# Power_Supply.net
KiCad netlist of a schematic drawn in Altium Designer
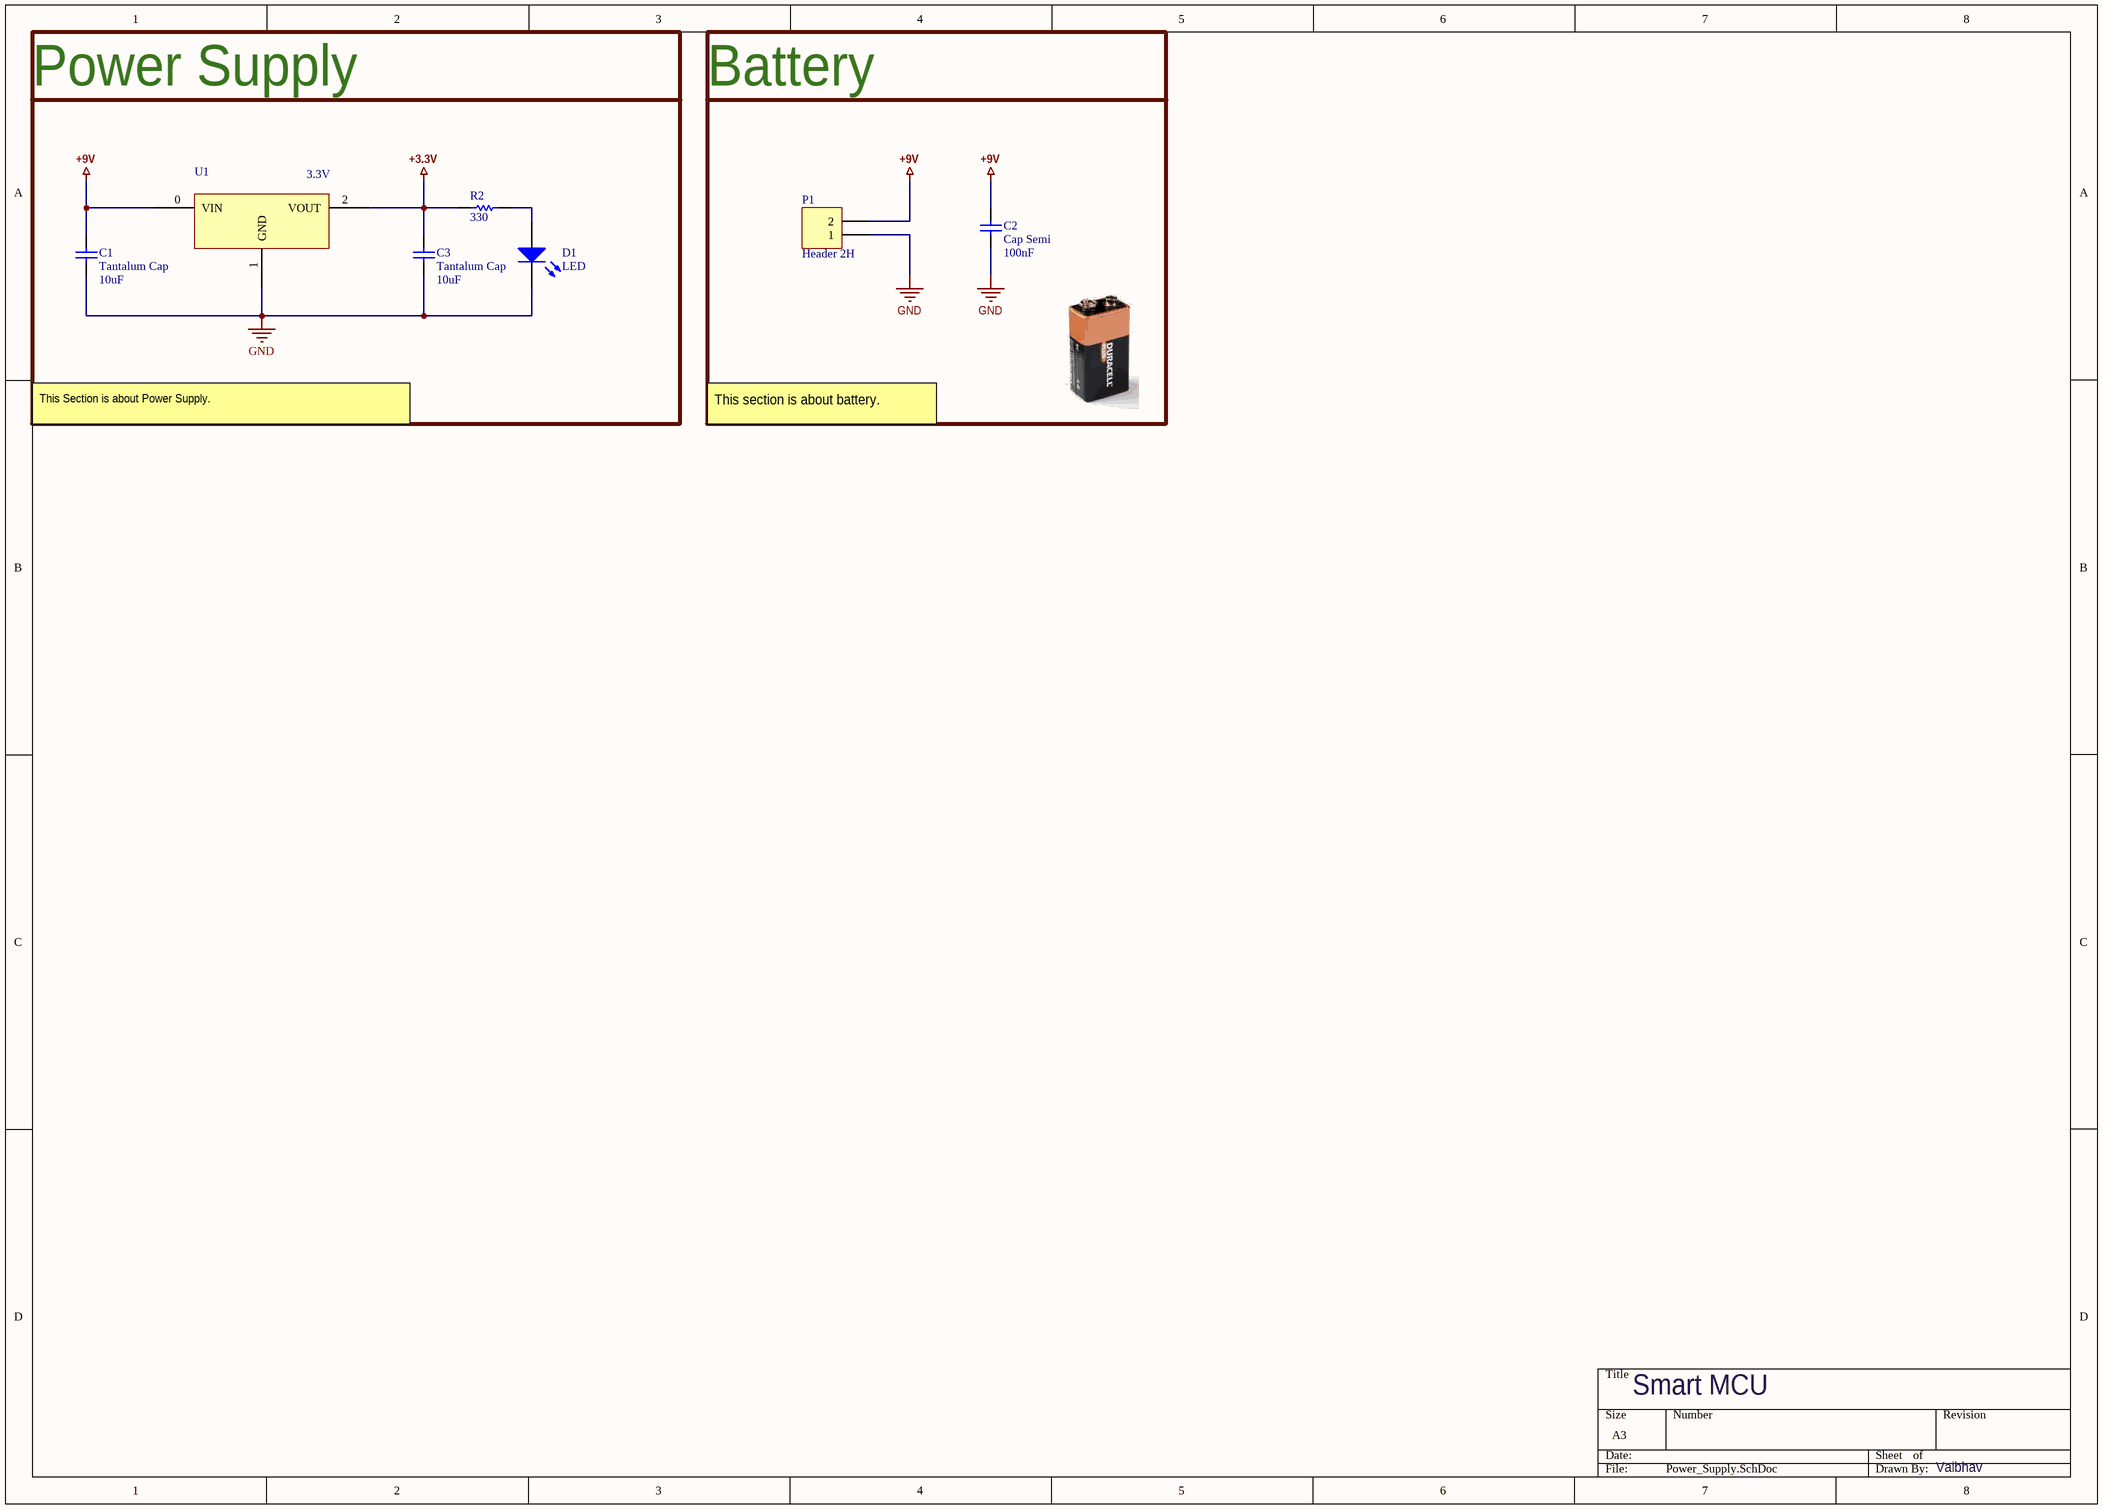
[diagram p0: Power_Supply.SchDoc]

(export (version "E")
  (design (tool "Eeschema 10.0.6"))
  (components
    (comp (ref "C1")
      (value "Tantalum Cap")
      (footprint "C1206")
      (description "Capacitor (Semiconductor SIM Model)")
      (fields (field (name "ALTIUM_VALUE") "10uF") (field (name "PUBLISHER") "Altium Limited"))
      (libsource (lib "Miscellaneous Devices") (part "Cap Semi"))
    )
    (comp (ref "C2")
      (value "Cap Semi")
      (footprint "C1206")
      (description "Capacitor (Semiconductor SIM Model)")
      (fields (field (name "ALTIUM_VALUE") "100nF") (field (name "PUBLISHER") "Altium Limited"))
      (libsource (lib "Miscellaneous Devices") (part "Cap Semi"))
    )
    (comp (ref "C3")
      (value "Tantalum Cap")
      (footprint "C1206")
      (description "Capacitor (Semiconductor SIM Model)")
      (fields (field (name "ALTIUM_VALUE") "10uF") (field (name "PUBLISHER") "Altium Limited"))
      (libsource (lib "Miscellaneous Devices") (part "Cap Semi"))
    )
    (comp (ref "D1")
      (value "LED")
      (footprint "MY_LED_0805")
      (description "Typical INFRARED GaAs LED")
      (fields (field (name "ASID PART NUMBER") "LED-AS"))
      (libsource (lib "Mylib+Rev+4") (part "LED"))
    )
    (comp (ref "P1")
      (value "Header 2H")
      (footprint "HDR1X2H")
      (description "Header, 2-Pin, Right Angle")
      (fields (field (name "PUBLISHER") "Altium Limited"))
      (libsource (lib "Miscellaneous Connectors") (part "Header 2H"))
    )
    (comp (ref "R2")
      (value "330")
      (footprint "MY_0805")
      (description "Standard resistor")
      (fields (field (name "ASID PART NUMBER") "Res-AS"))
      (libsource (lib "Mylib+Rev+4") (part "Res"))
    )
    (comp (ref "U1")
      (value "~")
      (footprint "4-Pin SOT")
      (fields (field (name "OUTPUT VOLTAG") "3.3V"))
      (libsource (lib "Smart MCU") (part "lm1117"))
    )
  )
  (nets
    (net (code "1") (name "+3.3V") (class "Default")
      (node (ref "C3") (pin "2") (pinfunction "2_2") (pintype "passive"))
      (node (ref "R2") (pin "1") (pinfunction "1_1") (pintype "passive"))
      (node (ref "U1") (pin "2") (pinfunction "VOUT_2") (pintype "passive"))
    )
    (net (code "2") (name "+9V") (class "Default")
      (node (ref "C1") (pin "2") (pinfunction "2_2") (pintype "passive"))
      (node (ref "C2") (pin "2") (pinfunction "2_2") (pintype "passive"))
      (node (ref "P1") (pin "2") (pinfunction "2_2") (pintype "passive"))
      (node (ref "U1") (pin "0") (pinfunction "VIN_0") (pintype "passive"))
    )
    (net (code "3") (name "GND") (class "Default")
      (node (ref "C1") (pin "1") (pinfunction "1_1") (pintype "passive"))
      (node (ref "C2") (pin "1") (pinfunction "1_1") (pintype "passive"))
      (node (ref "C3") (pin "1") (pinfunction "1_1") (pintype "passive"))
      (node (ref "D1") (pin "K") (pinfunction "K_K") (pintype "passive"))
      (node (ref "P1") (pin "1") (pinfunction "1_1") (pintype "passive"))
      (node (ref "U1") (pin "1") (pinfunction "GND_1") (pintype "passive"))
    )
    (net (code "4") (name "Net-(D1-PadA)") (class "Default")
      (node (ref "D1") (pin "A") (pinfunction "A_A") (pintype "passive"))
      (node (ref "R2") (pin "2") (pinfunction "2_2") (pintype "passive"))
    )
  )
)
